# 6_DIG.net
KiCad netlist of a schematic drawn in Altium Designer
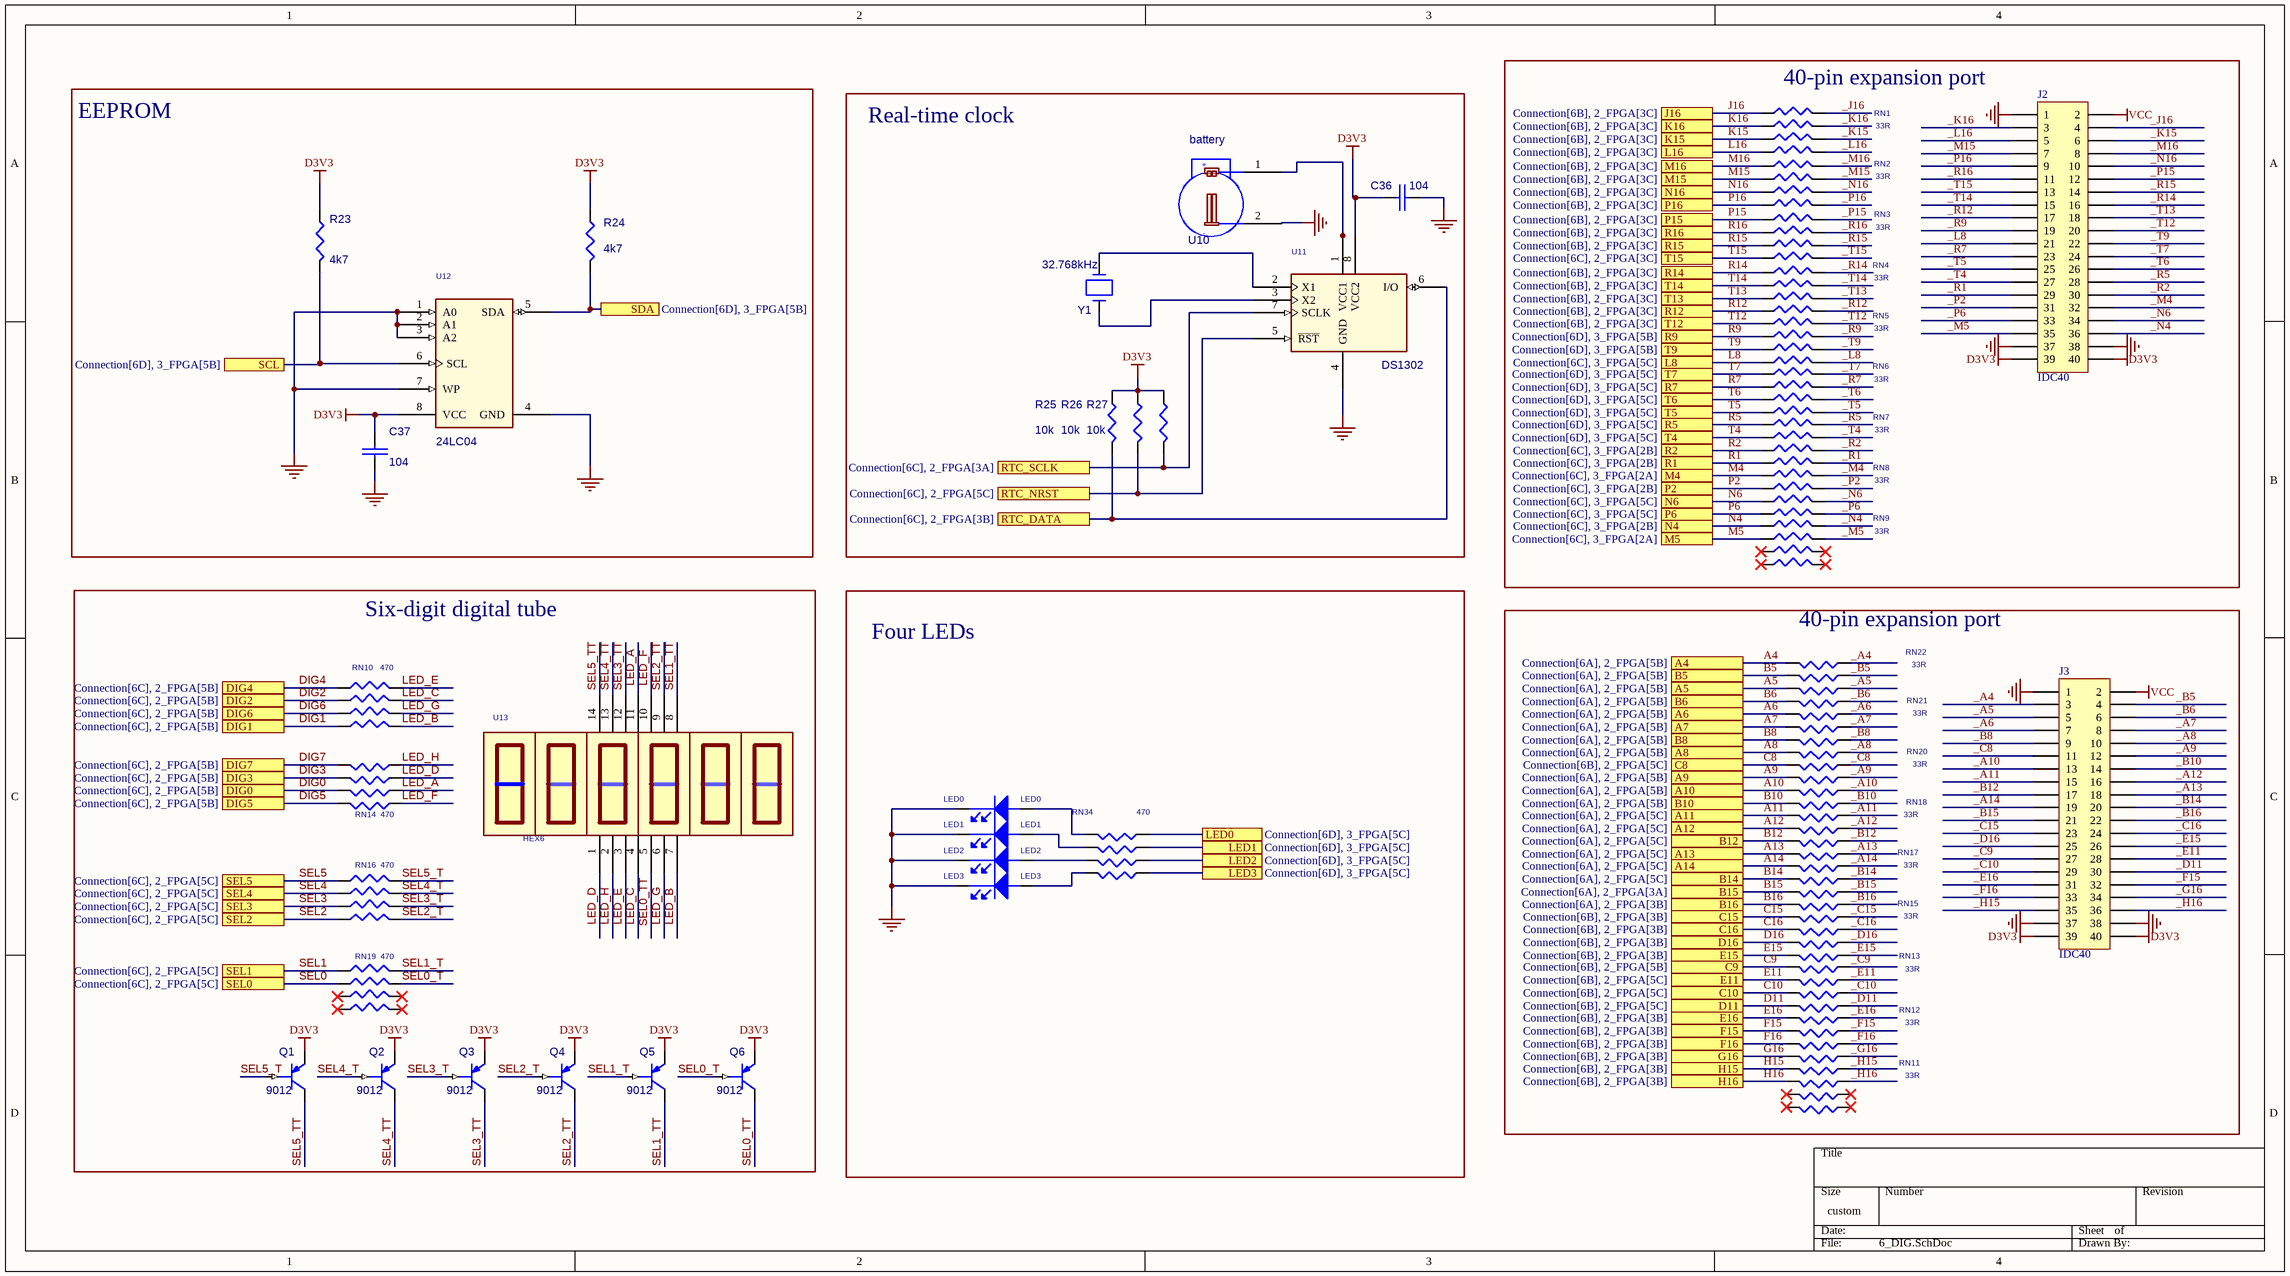
[diagram p0: 6_DIG.SchDoc]

(export (version "E")
  (design (tool "Eeschema 10.0.6"))
  (components
    (comp (ref "C36") (value "104") (footprint "0402") (libsource (lib "*") (part "C_Dup3")))
    (comp (ref "C37") (value "104") (footprint "0402") (libsource (lib "*") (part "C_Dup4")))
    (comp (ref "J2")
      (value "IDC40")
      (footprint "IDC-40J")
      (description "Header, 20-Pin, Dual row")
      (fields (field (name "PUBLISHER") "Altium Limited"))
      (libsource (lib "Miscellaneous Connectors") (part "MHDR2X20"))
    )
    (comp (ref "J3")
      (value "IDC40")
      (footprint "IDC-40J")
      (description "Header, 20-Pin, Dual row")
      (fields (field (name "PUBLISHER") "Altium Limited"))
      (libsource (lib "Miscellaneous Connectors") (part "MHDR2X20"))
    )
    (comp (ref "LED0") (value "LED0") (footprint "LEDSO") (libsource (lib "*") (part "LED_Dup1")))
    (comp (ref "LED1") (value "LED1") (footprint "LEDso") (libsource (lib "*") (part "LED_Dup1")))
    (comp (ref "LED2") (value "LED2") (footprint "LEDSO") (libsource (lib "*") (part "LED_Dup1")))
    (comp (ref "LED3") (value "LED3") (footprint "LEDSO") (libsource (lib "*") (part "LED_Dup1")))
    (comp (ref "Q1") (value "9012") (footprint "SOT23") (libsource (lib "*") (part "PNP")))
    (comp (ref "Q2") (value "9012") (footprint "SOT23") (libsource (lib "*") (part "PNP")))
    (comp (ref "Q3") (value "9012") (footprint "SOT23") (libsource (lib "*") (part "PNP")))
    (comp (ref "Q4") (value "9012") (footprint "SOT23") (libsource (lib "*") (part "PNP")))
    (comp (ref "Q5") (value "9012") (footprint "SOT23") (libsource (lib "*") (part "PNP")))
    (comp (ref "Q6") (value "9012") (footprint "SOT23") (libsource (lib "*") (part "PNP")))
    (comp (ref "R23") (value "4k7") (footprint "0603") (libsource (lib "*") (part "R_Dup6")))
    (comp (ref "R24") (value "4k7") (footprint "0603") (libsource (lib "*") (part "R_Dup6")))
    (comp (ref "R25") (value "10k") (footprint "0603") (libsource (lib "*") (part "R_Dup5")))
    (comp (ref "R26") (value "10k") (footprint "0603") (libsource (lib "*") (part "R_Dup5")))
    (comp (ref "R27") (value "10k") (footprint "0603") (libsource (lib "*") (part "R_Dup5")))
    (comp (ref "RN1") (value "33R") (footprint "RN-8P") (libsource (lib "*") (part "RN_Dup1")))
    (comp (ref "RN2") (value "33R") (footprint "RN-8P") (libsource (lib "*") (part "RN_Dup1")))
    (comp (ref "RN3") (value "33R") (footprint "RN-8P") (libsource (lib "*") (part "RN_Dup1")))
    (comp (ref "RN4") (value "33R") (footprint "RN-8P") (libsource (lib "*") (part "RN_Dup1")))
    (comp (ref "RN5") (value "33R") (footprint "RN-8P") (libsource (lib "*") (part "RN_Dup1")))
    (comp (ref "RN6") (value "33R") (footprint "RN-8P") (libsource (lib "*") (part "RN_Dup1")))
    (comp (ref "RN7") (value "33R") (footprint "RN-8P") (libsource (lib "*") (part "RN_Dup1")))
    (comp (ref "RN8") (value "33R") (footprint "RN-8P") (libsource (lib "*") (part "RN_Dup1")))
    (comp (ref "RN9") (value "33R") (footprint "RN-8P") (libsource (lib "*") (part "RN_Dup1")))
    (comp (ref "RN10") (value "470") (footprint "RN-8P") (libsource (lib "*") (part "RN")))
    (comp (ref "RN11") (value "33R") (footprint "RN-8P") (libsource (lib "*") (part "RN_Dup1")))
    (comp (ref "RN12") (value "33R") (footprint "RN-8P") (libsource (lib "*") (part "RN_Dup1")))
    (comp (ref "RN13") (value "33R") (footprint "RN-8P") (libsource (lib "*") (part "RN_Dup1")))
    (comp (ref "RN14") (value "470") (footprint "RN-8P") (libsource (lib "*") (part "RN")))
    (comp (ref "RN15") (value "33R") (footprint "RN-8P") (libsource (lib "*") (part "RN_Dup1")))
    (comp (ref "RN16") (value "470") (footprint "RN-8P") (libsource (lib "*") (part "RN")))
    (comp (ref "RN17") (value "33R") (footprint "RN-8P") (libsource (lib "*") (part "RN_Dup1")))
    (comp (ref "RN18") (value "33R") (footprint "RN-8P") (libsource (lib "*") (part "RN_Dup1")))
    (comp (ref "RN19") (value "470") (footprint "RN-8P") (libsource (lib "*") (part "RN")))
    (comp (ref "RN20") (value "33R") (footprint "RN-8P") (libsource (lib "*") (part "RN_Dup1")))
    (comp (ref "RN21") (value "33R") (footprint "RN-8P") (libsource (lib "*") (part "RN_Dup1")))
    (comp (ref "RN22") (value "33R") (footprint "RN-8P") (libsource (lib "*") (part "RN_Dup1")))
    (comp (ref "RN34") (value "470") (footprint "RN-8P") (libsource (lib "*") (part "RN")))
    (comp (ref "U10") (value "battery") (footprint "BATSO") (libsource (lib "*") (part "battery")))
    (comp (ref "U11")
      (value "DS1302")
      (fields (field (name "PART NUMBER") "TMP-13") (field (name "ICA_PARTNUM") "$$2098133$$DS1302S"))
      (libsource (lib "*") (part "DS1302_8SO"))
    )
    (comp (ref "U12") (value "24LC04") (libsource (lib "*") (part "24LC04B_0")))
    (comp (ref "U13") (value "HEX6") (libsource (lib "*") (part "HEX6")))
    (comp (ref "Y1") (value "32.768kHz") (libsource (lib "*") (part "ZTA")))
  )
  (nets
    (net (code "1") (name "/A4") (class "Default")
      (node (ref "RN22") (pin "5") (pinfunction "5_5") (pintype "passive"))
    )
    (net (code "2") (name "/A5") (class "Default")
      (node (ref "RN22") (pin "7") (pinfunction "7_7") (pintype "passive"))
    )
    (net (code "3") (name "/A6") (class "Default")
      (node (ref "RN21") (pin "5") (pinfunction "5_5") (pintype "passive"))
    )
    (net (code "4") (name "/A7") (class "Default")
      (node (ref "RN21") (pin "6") (pinfunction "6_6") (pintype "passive"))
    )
    (net (code "5") (name "/A8") (class "Default")
      (node (ref "RN21") (pin "8") (pinfunction "8_8") (pintype "passive"))
    )
    (net (code "6") (name "/A9") (class "Default")
      (node (ref "RN20") (pin "6") (pinfunction "6_6") (pintype "passive"))
    )
    (net (code "7") (name "/A10") (class "Default")
      (node (ref "RN20") (pin "7") (pinfunction "7_7") (pintype "passive"))
    )
    (net (code "8") (name "/A11") (class "Default")
      (node (ref "RN18") (pin "5") (pinfunction "5_5") (pintype "passive"))
    )
    (net (code "9") (name "/A12") (class "Default")
      (node (ref "RN18") (pin "6") (pinfunction "6_6") (pintype "passive"))
    )
    (net (code "10") (name "/A13") (class "Default")
      (node (ref "RN18") (pin "8") (pinfunction "8_8") (pintype "passive"))
    )
    (net (code "11") (name "/A14") (class "Default")
      (node (ref "RN17") (pin "5") (pinfunction "5_5") (pintype "passive"))
    )
    (net (code "12") (name "/B5") (class "Default")
      (node (ref "RN22") (pin "6") (pinfunction "6_6") (pintype "passive"))
    )
    (net (code "13") (name "/B6") (class "Default")
      (node (ref "RN22") (pin "8") (pinfunction "8_8") (pintype "passive"))
    )
    (net (code "14") (name "/B8") (class "Default")
      (node (ref "RN21") (pin "7") (pinfunction "7_7") (pintype "passive"))
    )
    (net (code "15") (name "/B10") (class "Default")
      (node (ref "RN20") (pin "8") (pinfunction "8_8") (pintype "passive"))
    )
    (net (code "16") (name "/B12") (class "Default")
      (node (ref "RN18") (pin "7") (pinfunction "7_7") (pintype "passive"))
    )
    (net (code "17") (name "/B14") (class "Default")
      (node (ref "RN17") (pin "6") (pinfunction "6_6") (pintype "passive"))
    )
    (net (code "18") (name "/B15") (class "Default")
      (node (ref "RN17") (pin "7") (pinfunction "7_7") (pintype "passive"))
    )
    (net (code "19") (name "/B16") (class "Default")
      (node (ref "RN17") (pin "8") (pinfunction "8_8") (pintype "passive"))
    )
    (net (code "20") (name "/C8") (class "Default")
      (node (ref "RN20") (pin "5") (pinfunction "5_5") (pintype "passive"))
    )
    (net (code "21") (name "/C9") (class "Default")
      (node (ref "RN13") (pin "5") (pinfunction "5_5") (pintype "passive"))
    )
    (net (code "22") (name "/C10") (class "Default")
      (node (ref "RN13") (pin "7") (pinfunction "7_7") (pintype "passive"))
    )
    (net (code "23") (name "/C15") (class "Default")
      (node (ref "RN15") (pin "5") (pinfunction "5_5") (pintype "passive"))
    )
    (net (code "24") (name "/C16") (class "Default")
      (node (ref "RN15") (pin "6") (pinfunction "6_6") (pintype "passive"))
    )
    (net (code "25") (name "/D11") (class "Default")
      (node (ref "RN13") (pin "8") (pinfunction "8_8") (pintype "passive"))
    )
    (net (code "26") (name "/D16") (class "Default")
      (node (ref "RN15") (pin "7") (pinfunction "7_7") (pintype "passive"))
    )
    (net (code "27") (name "/DIG0") (class "Default")
      (node (ref "RN14") (pin "7") (pinfunction "7_7") (pintype "passive"))
    )
    (net (code "28") (name "/DIG1") (class "Default")
      (node (ref "RN10") (pin "5") (pinfunction "5_5") (pintype "passive"))
    )
    (net (code "29") (name "/DIG2") (class "Default")
      (node (ref "RN10") (pin "7") (pinfunction "7_7") (pintype "passive"))
    )
    (net (code "30") (name "/DIG3") (class "Default")
      (node (ref "RN14") (pin "6") (pinfunction "6_6") (pintype "passive"))
    )
    (net (code "31") (name "/DIG4") (class "Default")
      (node (ref "RN10") (pin "8") (pinfunction "8_8") (pintype "passive"))
    )
    (net (code "32") (name "/DIG5") (class "Default")
      (node (ref "RN14") (pin "8") (pinfunction "8_8") (pintype "passive"))
    )
    (net (code "33") (name "/DIG6") (class "Default")
      (node (ref "RN10") (pin "6") (pinfunction "6_6") (pintype "passive"))
    )
    (net (code "34") (name "/DIG7") (class "Default")
      (node (ref "RN14") (pin "5") (pinfunction "5_5") (pintype "passive"))
    )
    (net (code "35") (name "/E11") (class "Default")
      (node (ref "RN13") (pin "6") (pinfunction "6_6") (pintype "passive"))
    )
    (net (code "36") (name "/E15") (class "Default")
      (node (ref "RN15") (pin "8") (pinfunction "8_8") (pintype "passive"))
    )
    (net (code "37") (name "/E16") (class "Default")
      (node (ref "RN12") (pin "5") (pinfunction "5_5") (pintype "passive"))
    )
    (net (code "38") (name "/F15") (class "Default")
      (node (ref "RN12") (pin "6") (pinfunction "6_6") (pintype "passive"))
    )
    (net (code "39") (name "/F16") (class "Default")
      (node (ref "RN12") (pin "7") (pinfunction "7_7") (pintype "passive"))
    )
    (net (code "40") (name "/G16") (class "Default")
      (node (ref "RN12") (pin "8") (pinfunction "8_8") (pintype "passive"))
    )
    (net (code "41") (name "/H15") (class "Default")
      (node (ref "RN11") (pin "5") (pinfunction "5_5") (pintype "passive"))
    )
    (net (code "42") (name "/H16") (class "Default")
      (node (ref "RN11") (pin "6") (pinfunction "6_6") (pintype "passive"))
    )
    (net (code "43") (name "/J16") (class "Default")
      (node (ref "RN1") (pin "1") (pinfunction "1_1") (pintype "passive"))
    )
    (net (code "44") (name "/K15") (class "Default")
      (node (ref "RN1") (pin "3") (pinfunction "3_3") (pintype "passive"))
    )
    (net (code "45") (name "/K16") (class "Default")
      (node (ref "RN1") (pin "2") (pinfunction "2_2") (pintype "passive"))
    )
    (net (code "46") (name "/L8") (class "Default")
      (node (ref "RN5") (pin "4") (pinfunction "4_4") (pintype "passive"))
    )
    (net (code "47") (name "/L16") (class "Default")
      (node (ref "RN1") (pin "4") (pinfunction "4_4") (pintype "passive"))
    )
    (net (code "48") (name "/LED0") (class "Default")
      (node (ref "RN34") (pin "4") (pinfunction "4_4") (pintype "passive"))
    )
    (net (code "49") (name "/LED1") (class "Default")
      (node (ref "RN34") (pin "3") (pinfunction "3_3") (pintype "passive"))
    )
    (net (code "50") (name "/LED2") (class "Default")
      (node (ref "RN34") (pin "2") (pinfunction "2_2") (pintype "passive"))
    )
    (net (code "51") (name "/LED3") (class "Default")
      (node (ref "RN34") (pin "1") (pinfunction "1_1") (pintype "passive"))
    )
    (net (code "52") (name "/LED_A") (class "Default")
      (node (ref "RN14") (pin "2") (pinfunction "2_2") (pintype "passive"))
      (node (ref "U13") (pin "11") (pinfunction "11_11") (pintype "passive"))
    )
    (net (code "53") (name "/LED_B") (class "Default")
      (node (ref "RN10") (pin "4") (pinfunction "4_4") (pintype "passive"))
      (node (ref "U13") (pin "7") (pinfunction "7_7") (pintype "passive"))
    )
    (net (code "54") (name "/LED_C") (class "Default")
      (node (ref "RN10") (pin "2") (pinfunction "2_2") (pintype "passive"))
      (node (ref "U13") (pin "4") (pinfunction "4_4") (pintype "passive"))
    )
    (net (code "55") (name "/LED_D") (class "Default")
      (node (ref "RN14") (pin "3") (pinfunction "3_3") (pintype "passive"))
      (node (ref "U13") (pin "1") (pinfunction "1_1") (pintype "passive"))
    )
    (net (code "56") (name "/LED_E") (class "Default")
      (node (ref "RN10") (pin "1") (pinfunction "1_1") (pintype "passive"))
      (node (ref "U13") (pin "3") (pinfunction "3_3") (pintype "passive"))
    )
    (net (code "57") (name "/LED_F") (class "Default")
      (node (ref "RN14") (pin "1") (pinfunction "1_1") (pintype "passive"))
      (node (ref "U13") (pin "10") (pinfunction "10_10") (pintype "passive"))
    )
    (net (code "58") (name "/LED_G") (class "Default")
      (node (ref "RN10") (pin "3") (pinfunction "3_3") (pintype "passive"))
      (node (ref "U13") (pin "6") (pinfunction "6_6") (pintype "passive"))
    )
    (net (code "59") (name "/LED_H") (class "Default")
      (node (ref "RN14") (pin "4") (pinfunction "4_4") (pintype "passive"))
      (node (ref "U13") (pin "2") (pinfunction "2_2") (pintype "passive"))
    )
    (net (code "60") (name "/M4") (class "Default")
      (node (ref "RN8") (pin "1") (pinfunction "1_1") (pintype "passive"))
    )
    (net (code "61") (name "/M5") (class "Default")
      (node (ref "RN9") (pin "2") (pinfunction "2_2") (pintype "passive"))
    )
    (net (code "62") (name "/M15") (class "Default")
      (node (ref "RN2") (pin "2") (pinfunction "2_2") (pintype "passive"))
    )
    (net (code "63") (name "/M16") (class "Default")
      (node (ref "RN2") (pin "1") (pinfunction "1_1") (pintype "passive"))
    )
    (net (code "64") (name "/N4") (class "Default")
      (node (ref "RN9") (pin "1") (pinfunction "1_1") (pintype "passive"))
    )
    (net (code "65") (name "/N6") (class "Default")
      (node (ref "RN8") (pin "3") (pinfunction "3_3") (pintype "passive"))
    )
    (net (code "66") (name "/N16") (class "Default")
      (node (ref "RN2") (pin "3") (pinfunction "3_3") (pintype "passive"))
    )
    (net (code "67") (name "/P2") (class "Default")
      (node (ref "RN8") (pin "2") (pinfunction "2_2") (pintype "passive"))
    )
    (net (code "68") (name "/P6") (class "Default")
      (node (ref "RN8") (pin "4") (pinfunction "4_4") (pintype "passive"))
    )
    (net (code "69") (name "/P15") (class "Default")
      (node (ref "RN3") (pin "1") (pinfunction "1_1") (pintype "passive"))
    )
    (net (code "70") (name "/P16") (class "Default")
      (node (ref "RN2") (pin "4") (pinfunction "4_4") (pintype "passive"))
    )
    (net (code "71") (name "/R1") (class "Default")
      (node (ref "RN7") (pin "4") (pinfunction "4_4") (pintype "passive"))
    )
    (net (code "72") (name "/R2") (class "Default")
      (node (ref "RN7") (pin "3") (pinfunction "3_3") (pintype "passive"))
    )
    (net (code "73") (name "/R5") (class "Default")
      (node (ref "RN7") (pin "1") (pinfunction "1_1") (pintype "passive"))
    )
    (net (code "74") (name "/R7") (class "Default")
      (node (ref "RN6") (pin "2") (pinfunction "2_2") (pintype "passive"))
    )
    (net (code "75") (name "/R9") (class "Default")
      (node (ref "RN5") (pin "2") (pinfunction "2_2") (pintype "passive"))
    )
    (net (code "76") (name "/R12") (class "Default")
      (node (ref "RN4") (pin "4") (pinfunction "4_4") (pintype "passive"))
    )
    (net (code "77") (name "/R14") (class "Default")
      (node (ref "RN4") (pin "1") (pinfunction "1_1") (pintype "passive"))
    )
    (net (code "78") (name "/R15") (class "Default")
      (node (ref "RN3") (pin "3") (pinfunction "3_3") (pintype "passive"))
    )
    (net (code "79") (name "/R16") (class "Default")
      (node (ref "RN3") (pin "2") (pinfunction "2_2") (pintype "passive"))
    )
    (net (code "80") (name "/RTC_DATA") (class "Default")
      (node (ref "R25") (pin "2") (pinfunction "2_2") (pintype "passive"))
      (node (ref "U11") (pin "6") (pinfunction "I/O_6") (pintype "bidirectional"))
    )
    (net (code "81") (name "/RTC_NRST") (class "Default")
      (node (ref "R26") (pin "2") (pinfunction "2_2") (pintype "passive"))
      (node (ref "U11") (pin "5") (pinfunction "~{RST}_5") (pintype "input"))
    )
    (net (code "82") (name "/RTC_SCLK") (class "Default")
      (node (ref "R27") (pin "2") (pinfunction "2_2") (pintype "passive"))
      (node (ref "U11") (pin "7") (pinfunction "SCLK_7") (pintype "input"))
    )
    (net (code "83") (name "/SCL") (class "Default")
      (node (ref "R23") (pin "2") (pinfunction "2_2") (pintype "passive"))
      (node (ref "U12") (pin "6") (pinfunction "SCL_6") (pintype "input"))
    )
    (net (code "84") (name "/SDA") (class "Default")
      (node (ref "R24") (pin "2") (pinfunction "2_2") (pintype "passive"))
      (node (ref "U12") (pin "5") (pinfunction "SDA_5") (pintype "bidirectional"))
    )
    (net (code "85") (name "/SEL0") (class "Default")
      (node (ref "RN19") (pin "7") (pinfunction "7_7") (pintype "passive"))
    )
    (net (code "86") (name "/SEL0_T") (class "Default")
      (node (ref "Q6") (pin "1") (pinfunction "BASE_1") (pintype "input"))
      (node (ref "RN19") (pin "2") (pinfunction "2_2") (pintype "passive"))
    )
    (net (code "87") (name "/SEL0_TT") (class "Default")
      (node (ref "Q6") (pin "3") (pinfunction "COLLECTOR_3") (pintype "passive"))
      (node (ref "U13") (pin "5") (pinfunction "5_5") (pintype "passive"))
    )
    (net (code "88") (name "/SEL1") (class "Default")
      (node (ref "RN19") (pin "8") (pinfunction "8_8") (pintype "passive"))
    )
    (net (code "89") (name "/SEL1_T") (class "Default")
      (node (ref "Q5") (pin "1") (pinfunction "BASE_1") (pintype "input"))
      (node (ref "RN19") (pin "1") (pinfunction "1_1") (pintype "passive"))
    )
    (net (code "90") (name "/SEL1_TT") (class "Default")
      (node (ref "Q5") (pin "3") (pinfunction "COLLECTOR_3") (pintype "passive"))
      (node (ref "U13") (pin "8") (pinfunction "8_8") (pintype "passive"))
    )
    (net (code "91") (name "/SEL2") (class "Default")
      (node (ref "RN16") (pin "5") (pinfunction "5_5") (pintype "passive"))
    )
    (net (code "92") (name "/SEL2_T") (class "Default")
      (node (ref "Q4") (pin "1") (pinfunction "BASE_1") (pintype "input"))
      (node (ref "RN16") (pin "4") (pinfunction "4_4") (pintype "passive"))
    )
    (net (code "93") (name "/SEL2_TT") (class "Default")
      (node (ref "Q4") (pin "3") (pinfunction "COLLECTOR_3") (pintype "passive"))
      (node (ref "U13") (pin "9") (pinfunction "9_9") (pintype "passive"))
    )
    (net (code "94") (name "/SEL3") (class "Default")
      (node (ref "RN16") (pin "6") (pinfunction "6_6") (pintype "passive"))
    )
    (net (code "95") (name "/SEL3_T") (class "Default")
      (node (ref "Q3") (pin "1") (pinfunction "BASE_1") (pintype "input"))
      (node (ref "RN16") (pin "3") (pinfunction "3_3") (pintype "passive"))
    )
    (net (code "96") (name "/SEL3_TT") (class "Default")
      (node (ref "Q3") (pin "3") (pinfunction "COLLECTOR_3") (pintype "passive"))
      (node (ref "U13") (pin "12") (pinfunction "12_12") (pintype "passive"))
    )
    (net (code "97") (name "/SEL4") (class "Default")
      (node (ref "RN16") (pin "7") (pinfunction "7_7") (pintype "passive"))
    )
    (net (code "98") (name "/SEL4_T") (class "Default")
      (node (ref "Q2") (pin "1") (pinfunction "BASE_1") (pintype "input"))
      (node (ref "RN16") (pin "2") (pinfunction "2_2") (pintype "passive"))
    )
    (net (code "99") (name "/SEL4_TT") (class "Default")
      (node (ref "Q2") (pin "3") (pinfunction "COLLECTOR_3") (pintype "passive"))
      (node (ref "U13") (pin "13") (pinfunction "13_13") (pintype "passive"))
    )
    (net (code "100") (name "/SEL5") (class "Default")
      (node (ref "RN16") (pin "8") (pinfunction "8_8") (pintype "passive"))
    )
    (net (code "101") (name "/SEL5_T") (class "Default")
      (node (ref "Q1") (pin "1") (pinfunction "BASE_1") (pintype "input"))
      (node (ref "RN16") (pin "1") (pinfunction "1_1") (pintype "passive"))
    )
    (net (code "102") (name "/SEL5_TT") (class "Default")
      (node (ref "Q1") (pin "3") (pinfunction "COLLECTOR_3") (pintype "passive"))
      (node (ref "U13") (pin "14") (pinfunction "14_14") (pintype "passive"))
    )
    (net (code "103") (name "/T4") (class "Default")
      (node (ref "RN7") (pin "2") (pinfunction "2_2") (pintype "passive"))
    )
    (net (code "104") (name "/T5") (class "Default")
      (node (ref "RN6") (pin "4") (pinfunction "4_4") (pintype "passive"))
    )
    (net (code "105") (name "/T6") (class "Default")
      (node (ref "RN6") (pin "3") (pinfunction "3_3") (pintype "passive"))
    )
    (net (code "106") (name "/T7") (class "Default")
      (node (ref "RN6") (pin "1") (pinfunction "1_1") (pintype "passive"))
    )
    (net (code "107") (name "/T9") (class "Default")
      (node (ref "RN5") (pin "3") (pinfunction "3_3") (pintype "passive"))
    )
    (net (code "108") (name "/T12") (class "Default")
      (node (ref "RN5") (pin "1") (pinfunction "1_1") (pintype "passive"))
    )
    (net (code "109") (name "/T13") (class "Default")
      (node (ref "RN4") (pin "3") (pinfunction "3_3") (pintype "passive"))
    )
    (net (code "110") (name "/T14") (class "Default")
      (node (ref "RN4") (pin "2") (pinfunction "2_2") (pintype "passive"))
    )
    (net (code "111") (name "/T15") (class "Default")
      (node (ref "RN3") (pin "4") (pinfunction "4_4") (pintype "passive"))
    )
    (net (code "112") (name "/_A4") (class "Default")
      (node (ref "J3") (pin "3") (pinfunction "3_3") (pintype "passive"))
      (node (ref "RN22") (pin "4") (pinfunction "4_4") (pintype "passive"))
    )
    (net (code "113") (name "/_A5") (class "Default")
      (node (ref "J3") (pin "5") (pinfunction "5_5") (pintype "passive"))
      (node (ref "RN22") (pin "2") (pinfunction "2_2") (pintype "passive"))
    )
    (net (code "114") (name "/_A6") (class "Default")
      (node (ref "J3") (pin "7") (pinfunction "7_7") (pintype "passive"))
      (node (ref "RN21") (pin "4") (pinfunction "4_4") (pintype "passive"))
    )
    (net (code "115") (name "/_A7") (class "Default")
      (node (ref "J3") (pin "8") (pinfunction "8_8") (pintype "passive"))
      (node (ref "RN21") (pin "3") (pinfunction "3_3") (pintype "passive"))
    )
    (net (code "116") (name "/_A8") (class "Default")
      (node (ref "J3") (pin "10") (pinfunction "10_10") (pintype "passive"))
      (node (ref "RN21") (pin "1") (pinfunction "1_1") (pintype "passive"))
    )
    (net (code "117") (name "/_A9") (class "Default")
      (node (ref "J3") (pin "12") (pinfunction "12_12") (pintype "passive"))
      (node (ref "RN20") (pin "3") (pinfunction "3_3") (pintype "passive"))
    )
    (net (code "118") (name "/_A10") (class "Default")
      (node (ref "J3") (pin "13") (pinfunction "13_13") (pintype "passive"))
      (node (ref "RN20") (pin "2") (pinfunction "2_2") (pintype "passive"))
    )
    (net (code "119") (name "/_A11") (class "Default")
      (node (ref "J3") (pin "15") (pinfunction "15_15") (pintype "passive"))
      (node (ref "RN18") (pin "4") (pinfunction "4_4") (pintype "passive"))
    )
    (net (code "120") (name "/_A12") (class "Default")
      (node (ref "J3") (pin "16") (pinfunction "16_16") (pintype "passive"))
      (node (ref "RN18") (pin "3") (pinfunction "3_3") (pintype "passive"))
    )
    (net (code "121") (name "/_A13") (class "Default")
      (node (ref "J3") (pin "18") (pinfunction "18_18") (pintype "passive"))
      (node (ref "RN18") (pin "1") (pinfunction "1_1") (pintype "passive"))
    )
    (net (code "122") (name "/_A14") (class "Default")
      (node (ref "J3") (pin "19") (pinfunction "19_19") (pintype "passive"))
      (node (ref "RN17") (pin "4") (pinfunction "4_4") (pintype "passive"))
    )
    (net (code "123") (name "/_B5") (class "Default")
      (node (ref "J3") (pin "4") (pinfunction "4_4") (pintype "passive"))
      (node (ref "RN22") (pin "3") (pinfunction "3_3") (pintype "passive"))
    )
    (net (code "124") (name "/_B6") (class "Default")
      (node (ref "J3") (pin "6") (pinfunction "6_6") (pintype "passive"))
      (node (ref "RN22") (pin "1") (pinfunction "1_1") (pintype "passive"))
    )
    (net (code "125") (name "/_B8") (class "Default")
      (node (ref "J3") (pin "9") (pinfunction "9_9") (pintype "passive"))
      (node (ref "RN21") (pin "2") (pinfunction "2_2") (pintype "passive"))
    )
    (net (code "126") (name "/_B10") (class "Default")
      (node (ref "J3") (pin "14") (pinfunction "14_14") (pintype "passive"))
      (node (ref "RN20") (pin "1") (pinfunction "1_1") (pintype "passive"))
    )
    (net (code "127") (name "/_B12") (class "Default")
      (node (ref "J3") (pin "17") (pinfunction "17_17") (pintype "passive"))
      (node (ref "RN18") (pin "2") (pinfunction "2_2") (pintype "passive"))
    )
    (net (code "128") (name "/_B14") (class "Default")
      (node (ref "J3") (pin "20") (pinfunction "20_20") (pintype "passive"))
      (node (ref "RN17") (pin "3") (pinfunction "3_3") (pintype "passive"))
    )
    (net (code "129") (name "/_B15") (class "Default")
      (node (ref "J3") (pin "21") (pinfunction "21_21") (pintype "passive"))
      (node (ref "RN17") (pin "2") (pinfunction "2_2") (pintype "passive"))
    )
    (net (code "130") (name "/_B16") (class "Default")
      (node (ref "J3") (pin "22") (pinfunction "22_22") (pintype "passive"))
      (node (ref "RN17") (pin "1") (pinfunction "1_1") (pintype "passive"))
    )
    (net (code "131") (name "/_C8") (class "Default")
      (node (ref "J3") (pin "11") (pinfunction "11_11") (pintype "passive"))
      (node (ref "RN20") (pin "4") (pinfunction "4_4") (pintype "passive"))
    )
    (net (code "132") (name "/_C9") (class "Default")
      (node (ref "J3") (pin "27") (pinfunction "27_27") (pintype "passive"))
      (node (ref "RN13") (pin "4") (pinfunction "4_4") (pintype "passive"))
    )
    (net (code "133") (name "/_C10") (class "Default")
      (node (ref "J3") (pin "29") (pinfunction "29_29") (pintype "passive"))
      (node (ref "RN13") (pin "2") (pinfunction "2_2") (pintype "passive"))
    )
    (net (code "134") (name "/_C15") (class "Default")
      (node (ref "J3") (pin "23") (pinfunction "23_23") (pintype "passive"))
      (node (ref "RN15") (pin "4") (pinfunction "4_4") (pintype "passive"))
    )
    (net (code "135") (name "/_C16") (class "Default")
      (node (ref "J3") (pin "24") (pinfunction "24_24") (pintype "passive"))
      (node (ref "RN15") (pin "3") (pinfunction "3_3") (pintype "passive"))
    )
    (net (code "136") (name "/_D11") (class "Default")
      (node (ref "J3") (pin "30") (pinfunction "30_30") (pintype "passive"))
      (node (ref "RN13") (pin "1") (pinfunction "1_1") (pintype "passive"))
    )
    (net (code "137") (name "/_D16") (class "Default")
      (node (ref "J3") (pin "25") (pinfunction "25_25") (pintype "passive"))
      (node (ref "RN15") (pin "2") (pinfunction "2_2") (pintype "passive"))
    )
    (net (code "138") (name "/_E11") (class "Default")
      (node (ref "J3") (pin "28") (pinfunction "28_28") (pintype "passive"))
      (node (ref "RN13") (pin "3") (pinfunction "3_3") (pintype "passive"))
    )
    (net (code "139") (name "/_E15") (class "Default")
      (node (ref "J3") (pin "26") (pinfunction "26_26") (pintype "passive"))
      (node (ref "RN15") (pin "1") (pinfunction "1_1") (pintype "passive"))
    )
    (net (code "140") (name "/_E16") (class "Default")
      (node (ref "J3") (pin "31") (pinfunction "31_31") (pintype "passive"))
      (node (ref "RN12") (pin "4") (pinfunction "4_4") (pintype "passive"))
    )
    (net (code "141") (name "/_F15") (class "Default")
      (node (ref "J3") (pin "32") (pinfunction "32_32") (pintype "passive"))
      (node (ref "RN12") (pin "3") (pinfunction "3_3") (pintype "passive"))
    )
    (net (code "142") (name "/_F16") (class "Default")
      (node (ref "J3") (pin "33") (pinfunction "33_33") (pintype "passive"))
      (node (ref "RN12") (pin "2") (pinfunction "2_2") (pintype "passive"))
    )
    (net (code "143") (name "/_G16") (class "Default")
      (node (ref "J3") (pin "34") (pinfunction "34_34") (pintype "passive"))
      (node (ref "RN12") (pin "1") (pinfunction "1_1") (pintype "passive"))
    )
    (net (code "144") (name "/_H15") (class "Default")
      (node (ref "J3") (pin "35") (pinfunction "35_35") (pintype "passive"))
      (node (ref "RN11") (pin "4") (pinfunction "4_4") (pintype "passive"))
    )
    (net (code "145") (name "/_H16") (class "Default")
      (node (ref "J3") (pin "36") (pinfunction "36_36") (pintype "passive"))
      (node (ref "RN11") (pin "3") (pinfunction "3_3") (pintype "passive"))
    )
    (net (code "146") (name "/_J16") (class "Default")
      (node (ref "J2") (pin "4") (pinfunction "4_4") (pintype "passive"))
      (node (ref "RN1") (pin "8") (pinfunction "8_8") (pintype "passive"))
    )
    (net (code "147") (name "/_K15") (class "Default")
      (node (ref "J2") (pin "6") (pinfunction "6_6") (pintype "passive"))
      (node (ref "RN1") (pin "6") (pinfunction "6_6") (pintype "passive"))
    )
    (net (code "148") (name "/_K16") (class "Default")
      (node (ref "J2") (pin "3") (pinfunction "3_3") (pintype "passive"))
      (node (ref "RN1") (pin "7") (pinfunction "7_7") (pintype "passive"))
    )
    (net (code "149") (name "/_L8") (class "Default")
      (node (ref "J2") (pin "21") (pinfunction "21_21") (pintype "passive"))
      (node (ref "RN5") (pin "5") (pinfunction "5_5") (pintype "passive"))
    )
    (net (code "150") (name "/_L16") (class "Default")
      (node (ref "J2") (pin "5") (pinfunction "5_5") (pintype "passive"))
      (node (ref "RN1") (pin "5") (pinfunction "5_5") (pintype "passive"))
    )
    (net (code "151") (name "/_M4") (class "Default")
      (node (ref "J2") (pin "32") (pinfunction "32_32") (pintype "passive"))
      (node (ref "RN8") (pin "8") (pinfunction "8_8") (pintype "passive"))
    )
    (net (code "152") (name "/_M5") (class "Default")
      (node (ref "J2") (pin "35") (pinfunction "35_35") (pintype "passive"))
      (node (ref "RN9") (pin "7") (pinfunction "7_7") (pintype "passive"))
    )
    (net (code "153") (name "/_M15") (class "Default")
      (node (ref "J2") (pin "7") (pinfunction "7_7") (pintype "passive"))
      (node (ref "RN2") (pin "7") (pinfunction "7_7") (pintype "passive"))
    )
    (net (code "154") (name "/_M16") (class "Default")
      (node (ref "J2") (pin "8") (pinfunction "8_8") (pintype "passive"))
      (node (ref "RN2") (pin "8") (pinfunction "8_8") (pintype "passive"))
    )
    (net (code "155") (name "/_N4") (class "Default")
      (node (ref "J2") (pin "36") (pinfunction "36_36") (pintype "passive"))
      (node (ref "RN9") (pin "8") (pinfunction "8_8") (pintype "passive"))
    )
    (net (code "156") (name "/_N6") (class "Default")
      (node (ref "J2") (pin "34") (pinfunction "34_34") (pintype "passive"))
      (node (ref "RN8") (pin "6") (pinfunction "6_6") (pintype "passive"))
    )
    (net (code "157") (name "/_N16") (class "Default")
      (node (ref "J2") (pin "10") (pinfunction "10_10") (pintype "passive"))
      (node (ref "RN2") (pin "6") (pinfunction "6_6") (pintype "passive"))
    )
    (net (code "158") (name "/_P2") (class "Default")
      (node (ref "J2") (pin "31") (pinfunction "31_31") (pintype "passive"))
      (node (ref "RN8") (pin "7") (pinfunction "7_7") (pintype "passive"))
    )
    (net (code "159") (name "/_P6") (class "Default")
      (node (ref "J2") (pin "33") (pinfunction "33_33") (pintype "passive"))
      (node (ref "RN8") (pin "5") (pinfunction "5_5") (pintype "passive"))
    )
    (net (code "160") (name "/_P15") (class "Default")
      (node (ref "J2") (pin "12") (pinfunction "12_12") (pintype "passive"))
      (node (ref "RN3") (pin "8") (pinfunction "8_8") (pintype "passive"))
    )
    (net (code "161") (name "/_P16") (class "Default")
      (node (ref "J2") (pin "9") (pinfunction "9_9") (pintype "passive"))
      (node (ref "RN2") (pin "5") (pinfunction "5_5") (pintype "passive"))
    )
    (net (code "162") (name "/_R1") (class "Default")
      (node (ref "J2") (pin "29") (pinfunction "29_29") (pintype "passive"))
      (node (ref "RN7") (pin "5") (pinfunction "5_5") (pintype "passive"))
    )
    (net (code "163") (name "/_R2") (class "Default")
      (node (ref "J2") (pin "30") (pinfunction "30_30") (pintype "passive"))
      (node (ref "RN7") (pin "6") (pinfunction "6_6") (pintype "passive"))
    )
    (net (code "164") (name "/_R5") (class "Default")
      (node (ref "J2") (pin "28") (pinfunction "28_28") (pintype "passive"))
      (node (ref "RN7") (pin "8") (pinfunction "8_8") (pintype "passive"))
    )
    (net (code "165") (name "/_R7") (class "Default")
      (node (ref "J2") (pin "23") (pinfunction "23_23") (pintype "passive"))
      (node (ref "RN6") (pin "7") (pinfunction "7_7") (pintype "passive"))
    )
    (net (code "166") (name "/_R9") (class "Default")
      (node (ref "J2") (pin "19") (pinfunction "19_19") (pintype "passive"))
      (node (ref "RN5") (pin "7") (pinfunction "7_7") (pintype "passive"))
    )
    (net (code "167") (name "/_R12") (class "Default")
      (node (ref "J2") (pin "17") (pinfunction "17_17") (pintype "passive"))
      (node (ref "RN4") (pin "5") (pinfunction "5_5") (pintype "passive"))
    )
    (net (code "168") (name "/_R14") (class "Default")
      (node (ref "J2") (pin "16") (pinfunction "16_16") (pintype "passive"))
      (node (ref "RN4") (pin "8") (pinfunction "8_8") (pintype "passive"))
    )
    (net (code "169") (name "/_R15") (class "Default")
      (node (ref "J2") (pin "14") (pinfunction "14_14") (pintype "passive"))
      (node (ref "RN3") (pin "6") (pinfunction "6_6") (pintype "passive"))
    )
    (net (code "170") (name "/_R16") (class "Default")
      (node (ref "J2") (pin "11") (pinfunction "11_11") (pintype "passive"))
      (node (ref "RN3") (pin "7") (pinfunction "7_7") (pintype "passive"))
    )
    (net (code "171") (name "/_T4") (class "Default")
      (node (ref "J2") (pin "27") (pinfunction "27_27") (pintype "passive"))
      (node (ref "RN7") (pin "7") (pinfunction "7_7") (pintype "passive"))
    )
    (net (code "172") (name "/_T5") (class "Default")
      (node (ref "J2") (pin "25") (pinfunction "25_25") (pintype "passive"))
      (node (ref "RN6") (pin "5") (pinfunction "5_5") (pintype "passive"))
    )
    (net (code "173") (name "/_T6") (class "Default")
      (node (ref "J2") (pin "26") (pinfunction "26_26") (pintype "passive"))
      (node (ref "RN6") (pin "6") (pinfunction "6_6") (pintype "passive"))
    )
    (net (code "174") (name "/_T7") (class "Default")
      (node (ref "J2") (pin "24") (pinfunction "24_24") (pintype "passive"))
      (node (ref "RN6") (pin "8") (pinfunction "8_8") (pintype "passive"))
    )
    (net (code "175") (name "/_T9") (class "Default")
      (node (ref "J2") (pin "22") (pinfunction "22_22") (pintype "passive"))
      (node (ref "RN5") (pin "6") (pinfunction "6_6") (pintype "passive"))
    )
    (net (code "176") (name "/_T12") (class "Default")
      (node (ref "J2") (pin "20") (pinfunction "20_20") (pintype "passive"))
      (node (ref "RN5") (pin "8") (pinfunction "8_8") (pintype "passive"))
    )
    (net (code "177") (name "/_T13") (class "Default")
      (node (ref "J2") (pin "18") (pinfunction "18_18") (pintype "passive"))
      (node (ref "RN4") (pin "6") (pinfunction "6_6") (pintype "passive"))
    )
    (net (code "178") (name "/_T14") (class "Default")
      (node (ref "J2") (pin "15") (pinfunction "15_15") (pintype "passive"))
      (node (ref "RN4") (pin "7") (pinfunction "7_7") (pintype "passive"))
    )
    (net (code "179") (name "/_T15") (class "Default")
      (node (ref "J2") (pin "13") (pinfunction "13_13") (pintype "passive"))
      (node (ref "RN3") (pin "5") (pinfunction "5_5") (pintype "passive"))
    )
    (net (code "180") (name "D3V3") (class "Default")
      (node (ref "C36") (pin "1") (pinfunction "1_1") (pintype "passive"))
      (node (ref "C37") (pin "1") (pinfunction "1_1") (pintype "passive"))
      (node (ref "J2") (pin "39") (pinfunction "39_39") (pintype "passive"))
      (node (ref "J2") (pin "40") (pinfunction "40_40") (pintype "passive"))
      (node (ref "J3") (pin "39") (pinfunction "39_39") (pintype "passive"))
      (node (ref "J3") (pin "40") (pinfunction "40_40") (pintype "passive"))
      (node (ref "Q1") (pin "2") (pinfunction "EMITTER_2") (pintype "passive"))
      (node (ref "Q2") (pin "2") (pinfunction "EMITTER_2") (pintype "passive"))
      (node (ref "Q3") (pin "2") (pinfunction "EMITTER_2") (pintype "passive"))
      (node (ref "Q4") (pin "2") (pinfunction "EMITTER_2") (pintype "passive"))
      (node (ref "Q5") (pin "2") (pinfunction "EMITTER_2") (pintype "passive"))
      (node (ref "Q6") (pin "2") (pinfunction "EMITTER_2") (pintype "passive"))
      (node (ref "R23") (pin "1") (pinfunction "1_1") (pintype "passive"))
      (node (ref "R24") (pin "1") (pinfunction "1_1") (pintype "passive"))
      (node (ref "R25") (pin "1") (pinfunction "1_1") (pintype "passive"))
      (node (ref "R26") (pin "1") (pinfunction "1_1") (pintype "passive"))
      (node (ref "R27") (pin "1") (pinfunction "1_1") (pintype "passive"))
      (node (ref "U11") (pin "8") (pinfunction "VCC2_8") (pintype "power_in"))
      (node (ref "U12") (pin "8") (pinfunction "VCC_8") (pintype "power_in"))
    )
    (net (code "181") (name "GND") (class "Default")
      (node (ref "C36") (pin "2") (pinfunction "2_2") (pintype "passive"))
      (node (ref "C37") (pin "2") (pinfunction "2_2") (pintype "passive"))
      (node (ref "J2") (pin "1") (pinfunction "1_1") (pintype "passive"))
      (node (ref "J2") (pin "37") (pinfunction "37_37") (pintype "passive"))
      (node (ref "J2") (pin "38") (pinfunction "38_38") (pintype "passive"))
      (node (ref "J3") (pin "1") (pinfunction "1_1") (pintype "passive"))
      (node (ref "J3") (pin "37") (pinfunction "37_37") (pintype "passive"))
      (node (ref "J3") (pin "38") (pinfunction "38_38") (pintype "passive"))
      (node (ref "LED0") (pin "2") (pinfunction "CATHODE_2") (pintype "passive"))
      (node (ref "LED1") (pin "2") (pinfunction "CATHODE_2") (pintype "passive"))
      (node (ref "LED2") (pin "2") (pinfunction "CATHODE_2") (pintype "passive"))
      (node (ref "LED3") (pin "2") (pinfunction "CATHODE_2") (pintype "passive"))
      (node (ref "U10") (pin "2") (pinfunction "GND_2") (pintype "passive"))
      (node (ref "U11") (pin "4") (pinfunction "GND_4") (pintype "power_in"))
      (node (ref "U12") (pin "1") (pinfunction "A0_1") (pintype "input"))
      (node (ref "U12") (pin "2") (pinfunction "A1_2") (pintype "input"))
      (node (ref "U12") (pin "3") (pinfunction "A2_3") (pintype "input"))
      (node (ref "U12") (pin "4") (pinfunction "GND_4") (pintype "power_in"))
      (node (ref "U12") (pin "7") (pinfunction "WP_7") (pintype "input"))
    )
    (net (code "182") (name "Net-(LED0-ANODE)") (class "Default")
      (node (ref "LED0") (pin "1") (pinfunction "ANODE_1") (pintype "passive"))
      (node (ref "RN34") (pin "5") (pinfunction "5_5") (pintype "passive"))
    )
    (net (code "183") (name "Net-(LED1-ANODE)") (class "Default")
      (node (ref "LED1") (pin "1") (pinfunction "ANODE_1") (pintype "passive"))
      (node (ref "RN34") (pin "6") (pinfunction "6_6") (pintype "passive"))
    )
    (net (code "184") (name "Net-(LED2-ANODE)") (class "Default")
      (node (ref "LED2") (pin "1") (pinfunction "ANODE_1") (pintype "passive"))
      (node (ref "RN34") (pin "7") (pinfunction "7_7") (pintype "passive"))
    )
    (net (code "185") (name "Net-(LED3-ANODE)") (class "Default")
      (node (ref "LED3") (pin "1") (pinfunction "ANODE_1") (pintype "passive"))
      (node (ref "RN34") (pin "8") (pinfunction "8_8") (pintype "passive"))
    )
    (net (code "186") (name "Net-(U10-VBAT)") (class "Default")
      (node (ref "U10") (pin "1") (pinfunction "VBAT_1") (pintype "passive"))
      (node (ref "U11") (pin "1") (pinfunction "VCC1_1") (pintype "power_in"))
    )
    (net (code "187") (name "Net-(U11-X1)") (class "Default")
      (node (ref "U11") (pin "2") (pinfunction "X1_2") (pintype "passive"))
      (node (ref "Y1") (pin "1") (pinfunction "1_1") (pintype "passive"))
    )
    (net (code "188") (name "Net-(U11-X2)") (class "Default")
      (node (ref "U11") (pin "3") (pinfunction "X2_3") (pintype "passive"))
      (node (ref "Y1") (pin "2") (pinfunction "2_2") (pintype "passive"))
    )
    (net (code "189") (name "VCC") (class "Default")
      (node (ref "J2") (pin "2") (pinfunction "2_2") (pintype "passive"))
      (node (ref "J3") (pin "2") (pinfunction "2_2") (pintype "passive"))
    )
    (net (code "190") (name "unconnected-(RN9-Pad3)") (class "Default")
      (node (ref "RN9") (pin "3") (pinfunction "3_3") (pintype "passive+no_connect"))
    )
    (net (code "191") (name "unconnected-(RN9-Pad4)") (class "Default")
      (node (ref "RN9") (pin "4") (pinfunction "4_4") (pintype "passive+no_connect"))
    )
    (net (code "192") (name "unconnected-(RN9-Pad5)") (class "Default")
      (node (ref "RN9") (pin "5") (pinfunction "5_5") (pintype "passive+no_connect"))
    )
    (net (code "193") (name "unconnected-(RN9-Pad6)") (class "Default")
      (node (ref "RN9") (pin "6") (pinfunction "6_6") (pintype "passive+no_connect"))
    )
    (net (code "194") (name "unconnected-(RN11-Pad1)") (class "Default")
      (node (ref "RN11") (pin "1") (pinfunction "1_1") (pintype "passive+no_connect"))
    )
    (net (code "195") (name "unconnected-(RN11-Pad2)") (class "Default")
      (node (ref "RN11") (pin "2") (pinfunction "2_2") (pintype "passive+no_connect"))
    )
    (net (code "196") (name "unconnected-(RN11-Pad7)") (class "Default")
      (node (ref "RN11") (pin "7") (pinfunction "7_7") (pintype "passive+no_connect"))
    )
    (net (code "197") (name "unconnected-(RN11-Pad8)") (class "Default")
      (node (ref "RN11") (pin "8") (pinfunction "8_8") (pintype "passive+no_connect"))
    )
    (net (code "198") (name "unconnected-(RN19-Pad3)") (class "Default")
      (node (ref "RN19") (pin "3") (pinfunction "3_3") (pintype "passive+no_connect"))
    )
    (net (code "199") (name "unconnected-(RN19-Pad4)") (class "Default")
      (node (ref "RN19") (pin "4") (pinfunction "4_4") (pintype "passive+no_connect"))
    )
    (net (code "200") (name "unconnected-(RN19-Pad5)") (class "Default")
      (node (ref "RN19") (pin "5") (pinfunction "5_5") (pintype "passive+no_connect"))
    )
    (net (code "201") (name "unconnected-(RN19-Pad6)") (class "Default")
      (node (ref "RN19") (pin "6") (pinfunction "6_6") (pintype "passive+no_connect"))
    )
  )
)
